# ICAN-7006-USB.net
KiCad netlist of a schematic drawn in Altium Designer
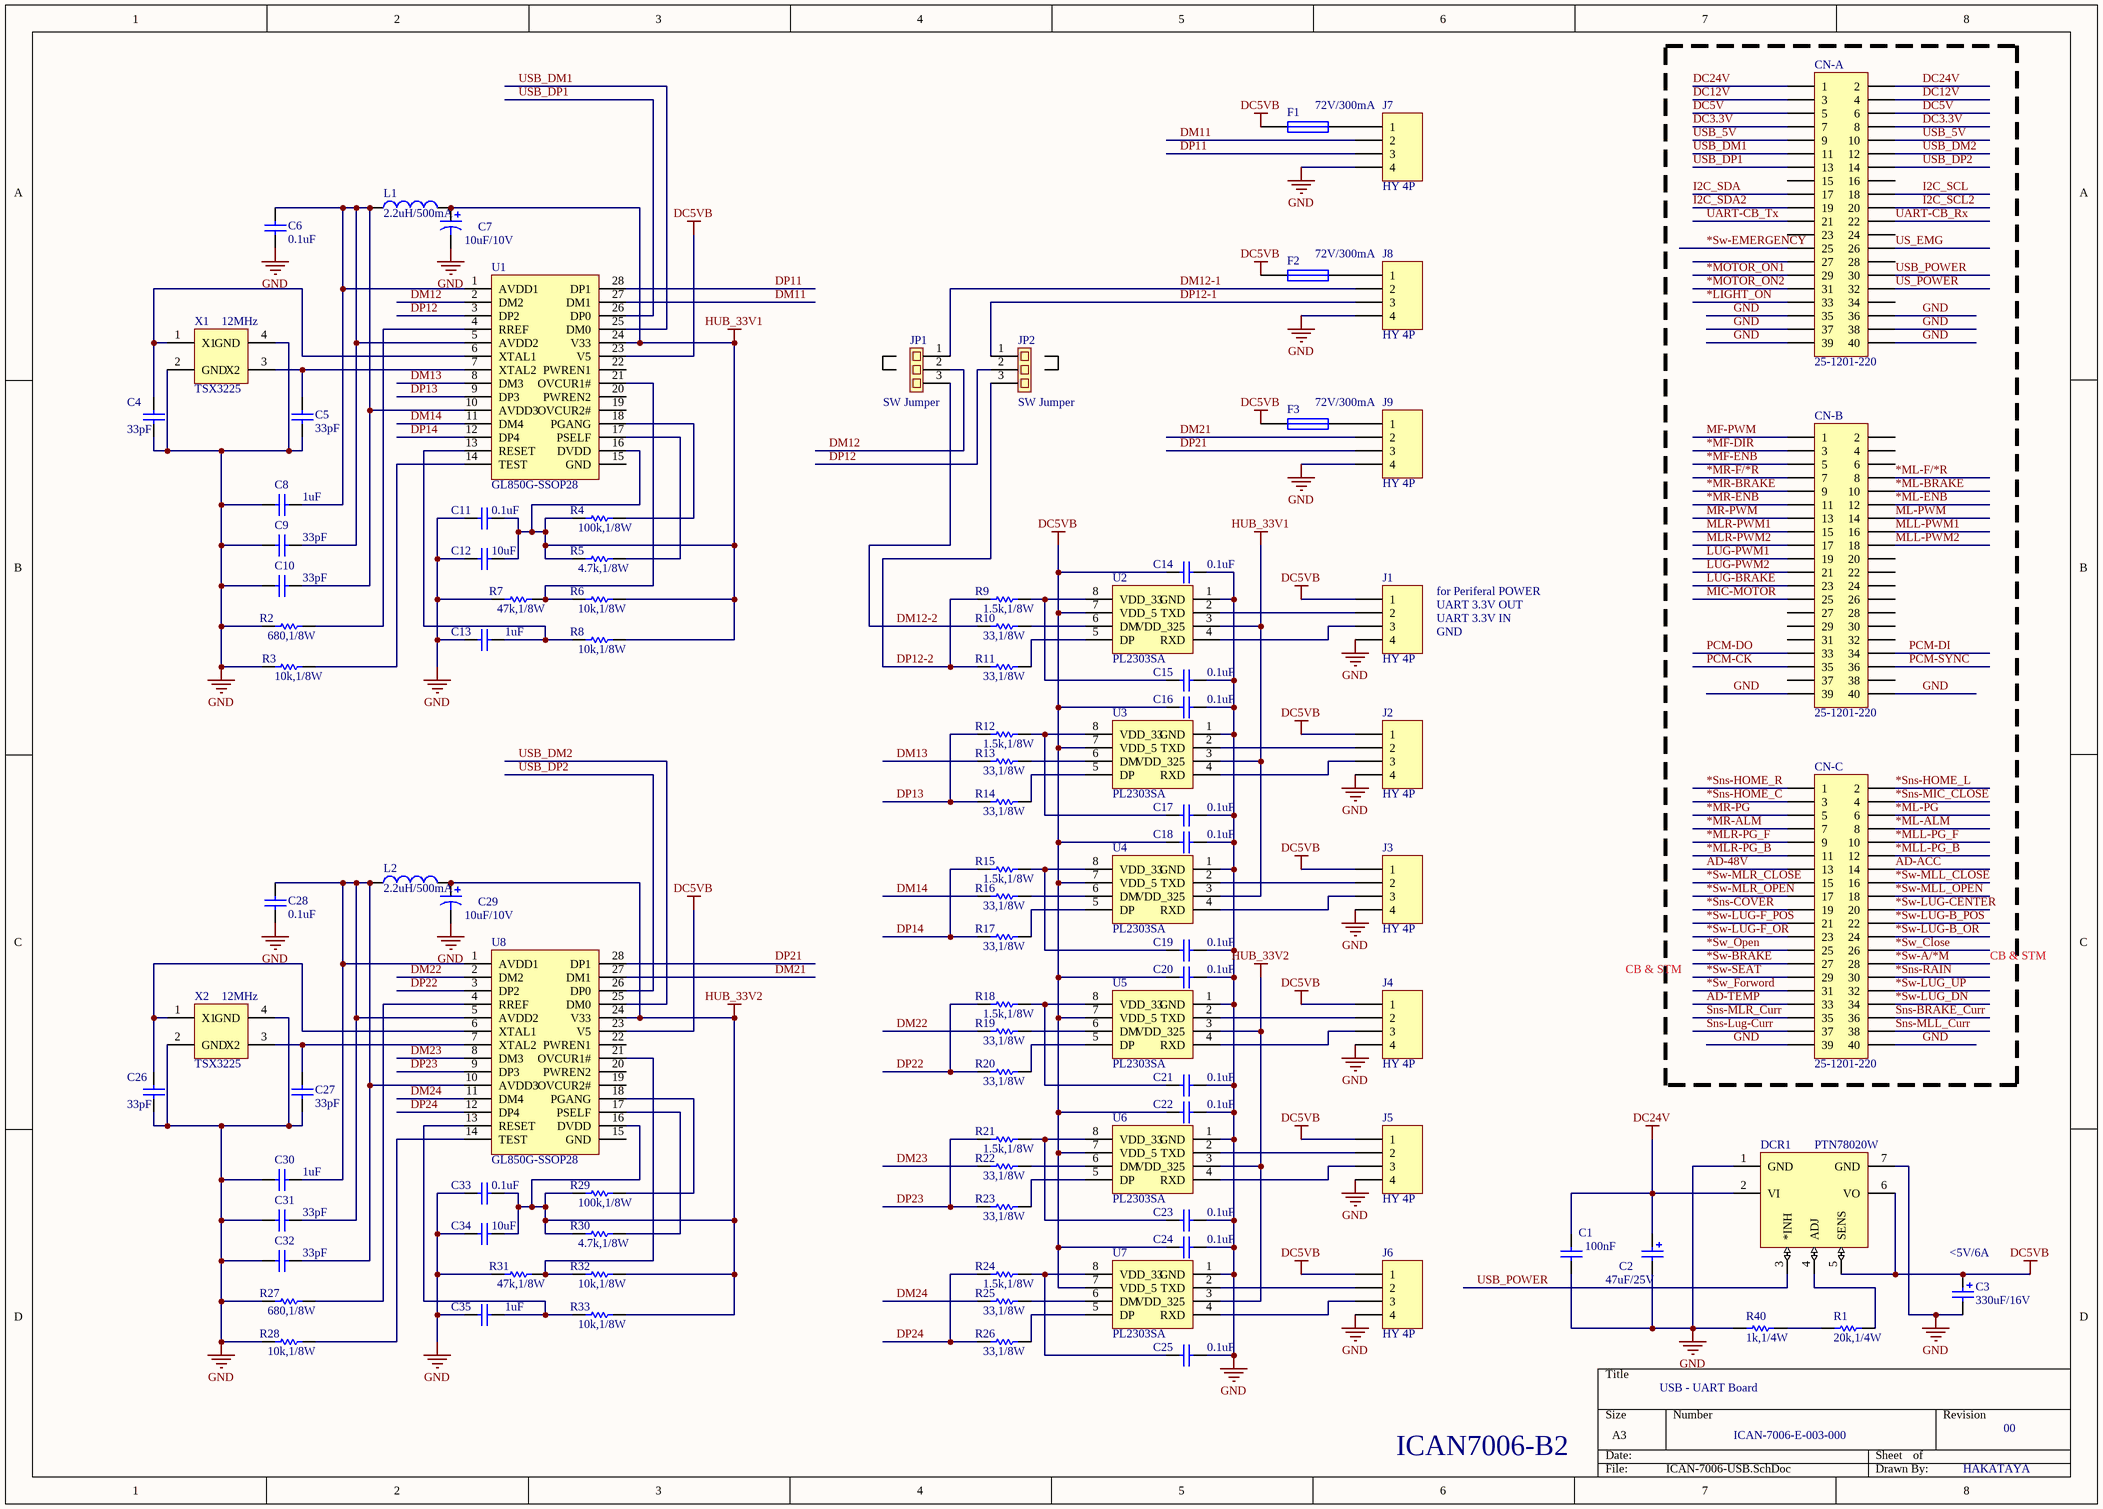
[diagram p0: ICAN-7006-USB.SchDoc]

(export (version "E")
  (design (tool "Eeschema 10.0.6"))
  (components
    (comp (ref "C1")
      (value "100nF")
      (footprint "HAKATAYA:[0805]2012")
      (description "Capacitor")
      (fields (field (name "PUBLISHER") "Altium Limited"))
      (libsource (lib "Miscellaneous Devices") (part "Cap"))
    )
    (comp (ref "C2")
      (value "47uF/25V")
      (footprint "HAKATAYA:Capa MH5 PITCH2.5mm")
      (description "Polarized Capacitor (Axial)")
      (fields (field (name "PUBLISHER") "Altium Limited"))
      (libsource (lib "Miscellaneous Devices") (part "Cap Pol2"))
    )
    (comp (ref "C3")
      (value "330uF/16V")
      (footprint "HAKATAYA:CAPA WXA PITCH 3.5mm")
      (description "Polarized Capacitor (Axial)")
      (fields (field (name "PUBLISHER") "Altium Limited"))
      (libsource (lib "Miscellaneous Devices") (part "Cap Pol2"))
    )
    (comp (ref "C4")
      (value "33pF")
      (footprint "HAKATAYA:[0805]2012")
      (description "Capacitor")
      (fields (field (name "PUBLISHER") "Altium Limited"))
      (libsource (lib "Miscellaneous Devices") (part "Cap Semi"))
    )
    (comp (ref "C5")
      (value "33pF")
      (footprint "HAKATAYA:[0805]2012")
      (description "Capacitor")
      (fields (field (name "PUBLISHER") "Altium Limited"))
      (libsource (lib "Miscellaneous Devices") (part "Cap Semi"))
    )
    (comp (ref "C6")
      (value "0.1uF")
      (footprint "HAKATAYA:[0805]2012")
      (description "Capacitor")
      (fields (field (name "PUBLISHER") "Altium Limited"))
      (libsource (lib "Miscellaneous Devices") (part "Cap Semi"))
    )
    (comp (ref "C7")
      (value "10uF/10V")
      (footprint "[0805]2012")
      (description "Polarized Capacitor (Surface Mount)")
      (fields (field (name "PUBLISHER") "Altium Limited"))
      (libsource (lib "Miscellaneous Devices") (part "Cap Pol3"))
    )
    (comp (ref "C8")
      (value "1uF")
      (footprint "[0805]2012")
      (description "Capacitor")
      (fields (field (name "PUBLISHER") "Altium Limited"))
      (libsource (lib "Miscellaneous Devices") (part "Cap Semi"))
    )
    (comp (ref "C9")
      (value "33pF")
      (footprint "HAKATAYA:[0805]2012")
      (description "Capacitor")
      (fields (field (name "PUBLISHER") "Altium Limited"))
      (libsource (lib "Miscellaneous Devices") (part "Cap Semi"))
    )
    (comp (ref "C10")
      (value "33pF")
      (footprint "HAKATAYA:[0805]2012")
      (description "Capacitor")
      (fields (field (name "PUBLISHER") "Altium Limited"))
      (libsource (lib "Miscellaneous Devices") (part "Cap Semi"))
    )
    (comp (ref "C11")
      (value "0.1uF")
      (footprint "HAKATAYA:[0805]2012")
      (description "Capacitor")
      (fields (field (name "PUBLISHER") "Altium Limited"))
      (libsource (lib "Miscellaneous Devices") (part "Cap Semi"))
    )
    (comp (ref "C12")
      (value "10uF")
      (footprint "[0805]2012")
      (description "Capacitor")
      (fields (field (name "PUBLISHER") "Altium Limited"))
      (libsource (lib "Miscellaneous Devices") (part "Cap Semi"))
    )
    (comp (ref "C13")
      (value "1uF")
      (footprint "[0805]2012")
      (description "Capacitor")
      (fields (field (name "PUBLISHER") "Altium Limited"))
      (libsource (lib "Miscellaneous Devices") (part "Cap Semi"))
    )
    (comp (ref "C14")
      (value "0.1uF")
      (footprint "HAKATAYA:[0805]2012")
      (description "Capacitor")
      (fields (field (name "PUBLISHER") "Altium Limited"))
      (libsource (lib "Miscellaneous Devices") (part "Cap Semi"))
    )
    (comp (ref "C15")
      (value "0.1uF")
      (footprint "HAKATAYA:[0805]2012")
      (description "Capacitor")
      (fields (field (name "PUBLISHER") "Altium Limited"))
      (libsource (lib "Miscellaneous Devices") (part "Cap Semi"))
    )
    (comp (ref "C16")
      (value "0.1uF")
      (footprint "[0805]2012")
      (description "Capacitor")
      (fields (field (name "PUBLISHER") "Altium Limited"))
      (libsource (lib "Miscellaneous Devices") (part "Cap Semi"))
    )
    (comp (ref "C17")
      (value "0.1uF")
      (footprint "[0805]2012")
      (description "Capacitor")
      (fields (field (name "PUBLISHER") "Altium Limited"))
      (libsource (lib "Miscellaneous Devices") (part "Cap Semi"))
    )
    (comp (ref "C18")
      (value "0.1uF")
      (footprint "[0805]2012")
      (description "Capacitor")
      (fields (field (name "PUBLISHER") "Altium Limited"))
      (libsource (lib "Miscellaneous Devices") (part "Cap Semi"))
    )
    (comp (ref "C19")
      (value "0.1uF")
      (footprint "[0805]2012")
      (description "Capacitor")
      (fields (field (name "PUBLISHER") "Altium Limited"))
      (libsource (lib "Miscellaneous Devices") (part "Cap Semi"))
    )
    (comp (ref "C20")
      (value "0.1uF")
      (footprint "[0805]2012")
      (description "Capacitor")
      (fields (field (name "PUBLISHER") "Altium Limited"))
      (libsource (lib "Miscellaneous Devices") (part "Cap Semi"))
    )
    (comp (ref "C21")
      (value "0.1uF")
      (footprint "[0805]2012")
      (description "Capacitor")
      (fields (field (name "PUBLISHER") "Altium Limited"))
      (libsource (lib "Miscellaneous Devices") (part "Cap Semi"))
    )
    (comp (ref "C22")
      (value "0.1uF")
      (footprint "[0805]2012")
      (description "Capacitor")
      (fields (field (name "PUBLISHER") "Altium Limited"))
      (libsource (lib "Miscellaneous Devices") (part "Cap Semi"))
    )
    (comp (ref "C23")
      (value "0.1uF")
      (footprint "[0805]2012")
      (description "Capacitor")
      (fields (field (name "PUBLISHER") "Altium Limited"))
      (libsource (lib "Miscellaneous Devices") (part "Cap Semi"))
    )
    (comp (ref "C24")
      (value "0.1uF")
      (footprint "[0805]2012")
      (description "Capacitor")
      (fields (field (name "PUBLISHER") "Altium Limited"))
      (libsource (lib "Miscellaneous Devices") (part "Cap Semi"))
    )
    (comp (ref "C25")
      (value "0.1uF")
      (footprint "[0805]2012")
      (description "Capacitor")
      (fields (field (name "PUBLISHER") "Altium Limited"))
      (libsource (lib "Miscellaneous Devices") (part "Cap Semi"))
    )
    (comp (ref "C26")
      (value "33pF")
      (footprint "HAKATAYA:[0805]2012")
      (description "Capacitor")
      (fields (field (name "PUBLISHER") "Altium Limited"))
      (libsource (lib "Miscellaneous Devices") (part "Cap Semi"))
    )
    (comp (ref "C27")
      (value "33pF")
      (footprint "HAKATAYA:[0805]2012")
      (description "Capacitor")
      (fields (field (name "PUBLISHER") "Altium Limited"))
      (libsource (lib "Miscellaneous Devices") (part "Cap Semi"))
    )
    (comp (ref "C28")
      (value "0.1uF")
      (footprint "[0805]2012")
      (description "Capacitor")
      (fields (field (name "PUBLISHER") "Altium Limited"))
      (libsource (lib "Miscellaneous Devices") (part "Cap Semi"))
    )
    (comp (ref "C29")
      (value "10uF/10V")
      (footprint "[0805]2012")
      (description "Polarized Capacitor (Surface Mount)")
      (fields (field (name "PUBLISHER") "Altium Limited"))
      (libsource (lib "Miscellaneous Devices") (part "Cap Pol3"))
    )
    (comp (ref "C30")
      (value "1uF")
      (footprint "[0805]2012")
      (description "Capacitor")
      (fields (field (name "PUBLISHER") "Altium Limited"))
      (libsource (lib "Miscellaneous Devices") (part "Cap Semi"))
    )
    (comp (ref "C31")
      (value "33pF")
      (footprint "HAKATAYA:[0805]2012")
      (description "Capacitor")
      (fields (field (name "PUBLISHER") "Altium Limited"))
      (libsource (lib "Miscellaneous Devices") (part "Cap Semi"))
    )
    (comp (ref "C32")
      (value "33pF")
      (footprint "HAKATAYA:[0805]2012")
      (description "Capacitor")
      (fields (field (name "PUBLISHER") "Altium Limited"))
      (libsource (lib "Miscellaneous Devices") (part "Cap Semi"))
    )
    (comp (ref "C33")
      (value "0.1uF")
      (footprint "[0805]2012")
      (description "Capacitor")
      (fields (field (name "PUBLISHER") "Altium Limited"))
      (libsource (lib "Miscellaneous Devices") (part "Cap Semi"))
    )
    (comp (ref "C34")
      (value "10uF")
      (footprint "[0805]2012")
      (description "Capacitor")
      (fields (field (name "PUBLISHER") "Altium Limited"))
      (libsource (lib "Miscellaneous Devices") (part "Cap Semi"))
    )
    (comp (ref "C35")
      (value "1uF")
      (footprint "[0805]2012")
      (description "Capacitor")
      (fields (field (name "PUBLISHER") "Altium Limited"))
      (libsource (lib "Miscellaneous Devices") (part "Cap Semi"))
    )
    (comp (ref "CN-A")
      (value "25-1201-220")
      (footprint "HDR2X20")
      (description "Header, 20-Pin, Dual row")
      (fields (field (name "PUBLISHER") "Altium Limited"))
      (libsource (lib "Miscellaneous Connectors") (part "Header 20X2"))
    )
    (comp (ref "CN-B")
      (value "25-1201-220")
      (footprint "HDR2X20")
      (description "Header, 20-Pin, Dual row")
      (fields (field (name "PUBLISHER") "Altium Limited"))
      (libsource (lib "Miscellaneous Connectors") (part "Header 20X2"))
    )
    (comp (ref "CN-C")
      (value "25-1201-220")
      (footprint "HDR2X20")
      (description "Header, 20-Pin, Dual row")
      (fields (field (name "PUBLISHER") "Altium Limited"))
      (libsource (lib "Miscellaneous Connectors") (part "Header 20X2"))
    )
    (comp (ref "DCR1")
      (value "PTN78020W")
      (footprint "PTN78020")
      (description "REGURATOR")
      (libsource (lib "*") (part "PTN78020"))
    )
    (comp (ref "F1")
      (value "72V/300mA")
      (footprint "Miscellaneous Devices:CAPR5-4X5")
      (description "Fuse")
      (fields (field (name "PUBLISHER") "Altium Limited"))
      (libsource (lib "Miscellaneous Devices") (part "Fuse 1"))
    )
    (comp (ref "F2")
      (value "72V/300mA")
      (footprint "Miscellaneous Devices:CAPR5-4X5")
      (description "Fuse")
      (fields (field (name "PUBLISHER") "Altium Limited"))
      (libsource (lib "Miscellaneous Devices") (part "Fuse 1"))
    )
    (comp (ref "F3")
      (value "72V/300mA")
      (footprint "Miscellaneous Devices:CAPR5-4X5")
      (description "Fuse")
      (fields (field (name "PUBLISHER") "Altium Limited"))
      (libsource (lib "Miscellaneous Devices") (part "Fuse 1"))
    )
    (comp (ref "J1")
      (value "HY 4P")
      (footprint "HAKATAYA:HY-4AW")
      (description "Header, 4-Pin")
      (fields (field (name "PUBLISHER") "Altium Limited"))
      (libsource (lib "Miscellaneous Connectors") (part "Header 4"))
    )
    (comp (ref "J2")
      (value "HY 4P")
      (footprint "HAKATAYA:HY-4AW")
      (description "Header, 4-Pin")
      (fields (field (name "PUBLISHER") "Altium Limited"))
      (libsource (lib "Miscellaneous Connectors") (part "Header 4"))
    )
    (comp (ref "J3")
      (value "HY 4P")
      (footprint "HAKATAYA:HY-4AW")
      (description "Header, 4-Pin")
      (fields (field (name "PUBLISHER") "Altium Limited"))
      (libsource (lib "Miscellaneous Connectors") (part "Header 4"))
    )
    (comp (ref "J4")
      (value "HY 4P")
      (footprint "HAKATAYA:HY-4AW")
      (description "Header, 4-Pin")
      (fields (field (name "PUBLISHER") "Altium Limited"))
      (libsource (lib "Miscellaneous Connectors") (part "Header 4"))
    )
    (comp (ref "J5")
      (value "HY 4P")
      (footprint "HAKATAYA:HY-4AW")
      (description "Header, 4-Pin")
      (fields (field (name "PUBLISHER") "Altium Limited"))
      (libsource (lib "Miscellaneous Connectors") (part "Header 4"))
    )
    (comp (ref "J6")
      (value "HY 4P")
      (footprint "HAKATAYA:HY-4AW")
      (description "Header, 4-Pin")
      (fields (field (name "PUBLISHER") "Altium Limited"))
      (libsource (lib "Miscellaneous Connectors") (part "Header 4"))
    )
    (comp (ref "J7")
      (value "HY 4P")
      (footprint "HAKATAYA:HY-4AW")
      (description "Header, 4-Pin")
      (fields (field (name "PUBLISHER") "Altium Limited"))
      (libsource (lib "Miscellaneous Connectors") (part "Header 4"))
    )
    (comp (ref "J8")
      (value "HY 4P")
      (footprint "HAKATAYA:HY-4AW")
      (description "Header, 4-Pin")
      (fields (field (name "PUBLISHER") "Altium Limited"))
      (libsource (lib "Miscellaneous Connectors") (part "Header 4"))
    )
    (comp (ref "J9")
      (value "HY 4P")
      (footprint "HAKATAYA:HY-4AW")
      (description "Header, 4-Pin")
      (fields (field (name "PUBLISHER") "Altium Limited"))
      (libsource (lib "Miscellaneous Connectors") (part "Header 4"))
    )
    (comp (ref "JP1")
      (value "SW Jumper")
      (footprint "VR")
      (description "Jumper")
      (libsource (lib "") (part "SW Jumper_1"))
    )
    (comp (ref "JP2")
      (value "SW Jumper")
      (footprint "VR")
      (description "Jumper")
      (libsource (lib "HAKATAYA") (part "SW Jumper"))
    )
    (comp (ref "L1")
      (value "2.2uH/500mA")
      (footprint "HAKATAYA:[0805]2012")
      (description "Inductor")
      (fields (field (name "PUBLISHER") "Altium Limited"))
      (libsource (lib "Miscellaneous Devices") (part "Inductor"))
    )
    (comp (ref "L2")
      (value "2.2uH/500mA")
      (footprint "HAKATAYA:[0805]2012")
      (description "Inductor")
      (fields (field (name "PUBLISHER") "Altium Limited"))
      (libsource (lib "Miscellaneous Devices") (part "Inductor"))
    )
    (comp (ref "R1")
      (value "20k,1/4W")
      (footprint "[1206]3216")
      (description "Resistor")
      (fields (field (name "PUBLISHER") "Altium Limited"))
      (libsource (lib "Miscellaneous Devices") (part "Res1"))
    )
    (comp (ref "R2")
      (value "680,1/8W")
      (footprint "HAKATAYA:[0805]2012")
      (description "Resistor")
      (fields (field (name "PUBLISHER") "Altium Limited"))
      (libsource (lib "Miscellaneous Devices") (part "Res1"))
    )
    (comp (ref "R3")
      (value "10k,1/8W")
      (footprint "HAKATAYA:[0805]2012")
      (description "Resistor")
      (fields (field (name "PUBLISHER") "Altium Limited"))
      (libsource (lib "Miscellaneous Devices") (part "Res1"))
    )
    (comp (ref "R4")
      (value "100k,1/8W")
      (footprint "HAKATAYA:[0805]2012")
      (description "Resistor")
      (fields (field (name "PUBLISHER") "Altium Limited"))
      (libsource (lib "Miscellaneous Devices") (part "Res1"))
    )
    (comp (ref "R5")
      (value "4.7k,1/8W")
      (footprint "HAKATAYA:[0805]2012")
      (description "Resistor")
      (fields (field (name "PUBLISHER") "Altium Limited"))
      (libsource (lib "Miscellaneous Devices") (part "Res1"))
    )
    (comp (ref "R6")
      (value "10k,1/8W")
      (footprint "HAKATAYA:[0805]2012")
      (description "Resistor")
      (fields (field (name "PUBLISHER") "Altium Limited"))
      (libsource (lib "Miscellaneous Devices") (part "Res1"))
    )
    (comp (ref "R7")
      (value "47k,1/8W")
      (footprint "HAKATAYA:[0805]2012")
      (description "Resistor")
      (fields (field (name "PUBLISHER") "Altium Limited"))
      (libsource (lib "Miscellaneous Devices") (part "Res1"))
    )
    (comp (ref "R8")
      (value "10k,1/8W")
      (footprint "HAKATAYA:[0805]2012")
      (description "Resistor")
      (fields (field (name "PUBLISHER") "Altium Limited"))
      (libsource (lib "Miscellaneous Devices") (part "Res1"))
    )
    (comp (ref "R9")
      (value "1.5k,1/8W")
      (footprint "HAKATAYA:[0805]2012")
      (description "Resistor")
      (fields (field (name "PUBLISHER") "Altium Limited"))
      (libsource (lib "Miscellaneous Devices") (part "Res1"))
    )
    (comp (ref "R10")
      (value "33,1/8W")
      (footprint "HAKATAYA:[0805]2012")
      (description "Resistor")
      (fields (field (name "PUBLISHER") "Altium Limited"))
      (libsource (lib "Miscellaneous Devices") (part "Res1"))
    )
    (comp (ref "R11")
      (value "33,1/8W")
      (footprint "HAKATAYA:[0805]2012")
      (description "Resistor")
      (fields (field (name "PUBLISHER") "Altium Limited"))
      (libsource (lib "Miscellaneous Devices") (part "Res1"))
    )
    (comp (ref "R12")
      (value "1.5k,1/8W")
      (footprint "HAKATAYA:[0805]2012")
      (description "Resistor")
      (fields (field (name "PUBLISHER") "Altium Limited"))
      (libsource (lib "Miscellaneous Devices") (part "Res1"))
    )
    (comp (ref "R13")
      (value "33,1/8W")
      (footprint "HAKATAYA:[0805]2012")
      (description "Resistor")
      (fields (field (name "PUBLISHER") "Altium Limited"))
      (libsource (lib "Miscellaneous Devices") (part "Res1"))
    )
    (comp (ref "R14")
      (value "33,1/8W")
      (footprint "HAKATAYA:[0805]2012")
      (description "Resistor")
      (fields (field (name "PUBLISHER") "Altium Limited"))
      (libsource (lib "Miscellaneous Devices") (part "Res1"))
    )
    (comp (ref "R15")
      (value "1.5k,1/8W")
      (footprint "HAKATAYA:[0805]2012")
      (description "Resistor")
      (fields (field (name "PUBLISHER") "Altium Limited"))
      (libsource (lib "Miscellaneous Devices") (part "Res1"))
    )
    (comp (ref "R16")
      (value "33,1/8W")
      (footprint "HAKATAYA:[0805]2012")
      (description "Resistor")
      (fields (field (name "PUBLISHER") "Altium Limited"))
      (libsource (lib "Miscellaneous Devices") (part "Res1"))
    )
    (comp (ref "R17")
      (value "33,1/8W")
      (footprint "HAKATAYA:[0805]2012")
      (description "Resistor")
      (fields (field (name "PUBLISHER") "Altium Limited"))
      (libsource (lib "Miscellaneous Devices") (part "Res1"))
    )
    (comp (ref "R18")
      (value "1.5k,1/8W")
      (footprint "HAKATAYA:[0805]2012")
      (description "Resistor")
      (fields (field (name "PUBLISHER") "Altium Limited"))
      (libsource (lib "Miscellaneous Devices") (part "Res1"))
    )
    (comp (ref "R19")
      (value "33,1/8W")
      (footprint "HAKATAYA:[0805]2012")
      (description "Resistor")
      (fields (field (name "PUBLISHER") "Altium Limited"))
      (libsource (lib "Miscellaneous Devices") (part "Res1"))
    )
    (comp (ref "R20")
      (value "33,1/8W")
      (footprint "HAKATAYA:[0805]2012")
      (description "Resistor")
      (fields (field (name "PUBLISHER") "Altium Limited"))
      (libsource (lib "Miscellaneous Devices") (part "Res1"))
    )
    (comp (ref "R21")
      (value "1.5k,1/8W")
      (footprint "HAKATAYA:[0805]2012")
      (description "Resistor")
      (fields (field (name "PUBLISHER") "Altium Limited"))
      (libsource (lib "Miscellaneous Devices") (part "Res1"))
    )
    (comp (ref "R22")
      (value "33,1/8W")
      (footprint "HAKATAYA:[0805]2012")
      (description "Resistor")
      (fields (field (name "PUBLISHER") "Altium Limited"))
      (libsource (lib "Miscellaneous Devices") (part "Res1"))
    )
    (comp (ref "R23")
      (value "33,1/8W")
      (footprint "HAKATAYA:[0805]2012")
      (description "Resistor")
      (fields (field (name "PUBLISHER") "Altium Limited"))
      (libsource (lib "Miscellaneous Devices") (part "Res1"))
    )
    (comp (ref "R24")
      (value "1.5k,1/8W")
      (footprint "HAKATAYA:[0805]2012")
      (description "Resistor")
      (fields (field (name "PUBLISHER") "Altium Limited"))
      (libsource (lib "Miscellaneous Devices") (part "Res1"))
    )
    (comp (ref "R25")
      (value "33,1/8W")
      (footprint "HAKATAYA:[0805]2012")
      (description "Resistor")
      (fields (field (name "PUBLISHER") "Altium Limited"))
      (libsource (lib "Miscellaneous Devices") (part "Res1"))
    )
    (comp (ref "R26")
      (value "33,1/8W")
      (footprint "HAKATAYA:[0805]2012")
      (description "Resistor")
      (fields (field (name "PUBLISHER") "Altium Limited"))
      (libsource (lib "Miscellaneous Devices") (part "Res1"))
    )
    (comp (ref "R27")
      (value "680,1/8W")
      (footprint "HAKATAYA:[0805]2012")
      (description "Resistor")
      (fields (field (name "PUBLISHER") "Altium Limited"))
      (libsource (lib "Miscellaneous Devices") (part "Res1"))
    )
    (comp (ref "R28")
      (value "10k,1/8W")
      (footprint "HAKATAYA:[0805]2012")
      (description "Resistor")
      (fields (field (name "PUBLISHER") "Altium Limited"))
      (libsource (lib "Miscellaneous Devices") (part "Res1"))
    )
    (comp (ref "R29")
      (value "100k,1/8W")
      (footprint "HAKATAYA:[0805]2012")
      (description "Resistor")
      (fields (field (name "PUBLISHER") "Altium Limited"))
      (libsource (lib "Miscellaneous Devices") (part "Res1"))
    )
    (comp (ref "R30")
      (value "4.7k,1/8W")
      (footprint "HAKATAYA:[0805]2012")
      (description "Resistor")
      (fields (field (name "PUBLISHER") "Altium Limited"))
      (libsource (lib "Miscellaneous Devices") (part "Res1"))
    )
    (comp (ref "R31")
      (value "47k,1/8W")
      (footprint "HAKATAYA:[0805]2012")
      (description "Resistor")
      (fields (field (name "PUBLISHER") "Altium Limited"))
      (libsource (lib "Miscellaneous Devices") (part "Res1"))
    )
    (comp (ref "R32")
      (value "10k,1/8W")
      (footprint "HAKATAYA:[0805]2012")
      (description "Resistor")
      (fields (field (name "PUBLISHER") "Altium Limited"))
      (libsource (lib "Miscellaneous Devices") (part "Res1"))
    )
    (comp (ref "R33")
      (value "10k,1/8W")
      (footprint "HAKATAYA:[0805]2012")
      (description "Resistor")
      (fields (field (name "PUBLISHER") "Altium Limited"))
      (libsource (lib "Miscellaneous Devices") (part "Res1"))
    )
    (comp (ref "R40")
      (value "1k,1/4W")
      (footprint "[1206]3216")
      (description "Resistor")
      (fields (field (name "PUBLISHER") "Altium Limited"))
      (libsource (lib "Miscellaneous Devices") (part "Res1"))
    )
    (comp (ref "U1")
      (value "GL850G-SSOP28")
      (footprint "Microchip Footprints:SSOP-28")
      (description "HUB Controller")
      (libsource (lib "HAKATAYA") (part "IC28"))
    )
    (comp (ref "U2")
      (value "PL2303SA")
      (footprint "Microchip Footprints:SOIC150-8_L")
      (description "Serial Bridge")
      (libsource (lib "HAKATAYA") (part "IC8-WIDE"))
    )
    (comp (ref "U3")
      (value "PL2303SA")
      (footprint "Microchip Footprints:SOIC150-8_L")
      (description "Serial Bridge")
      (libsource (lib "HAKATAYA") (part "IC8-WIDE"))
    )
    (comp (ref "U4")
      (value "PL2303SA")
      (footprint "Microchip Footprints:SOIC150-8_L")
      (description "Serial Bridge")
      (libsource (lib "HAKATAYA") (part "IC8-WIDE"))
    )
    (comp (ref "U5")
      (value "PL2303SA")
      (footprint "Microchip Footprints:SOIC150-8_L")
      (description "Serial Bridge")
      (libsource (lib "HAKATAYA") (part "IC8-WIDE"))
    )
    (comp (ref "U6")
      (value "PL2303SA")
      (footprint "Microchip Footprints:SOIC150-8_L")
      (description "Serial Bridge")
      (libsource (lib "HAKATAYA") (part "IC8-WIDE"))
    )
    (comp (ref "U7")
      (value "PL2303SA")
      (footprint "Microchip Footprints:SOIC150-8_L")
      (description "Serial Bridge")
      (libsource (lib "HAKATAYA") (part "IC8-WIDE"))
    )
    (comp (ref "U8")
      (value "GL850G-SSOP28")
      (footprint "Microchip Footprints:SSOP-28")
      (libsource (lib "HAKATAYA") (part "IC28"))
    )
    (comp (ref "X1")
      (value "TSX3225")
      (footprint "HAKATAYA:XTAL 3225")
      (description "Crystal Oscillator")
      (libsource (lib "HAKATAYA") (part "IC4 WIDE"))
    )
    (comp (ref "X2")
      (value "TSX3225")
      (footprint "HAKATAYA:XTAL 3225")
      (description "Crystal Oscillator")
      (libsource (lib "HAKATAYA") (part "IC4 WIDE"))
    )
  )
  (nets
    (net (code "1") (name "/*LIGHT_ON") (class "Default")
      (node (ref "CN-A") (pin "33") (pinfunction "33_33") (pintype "passive"))
    )
    (net (code "2") (name "/*MF-DIR") (class "Default")
      (node (ref "CN-B") (pin "3") (pinfunction "3_3") (pintype "passive"))
    )
    (net (code "3") (name "/*MF-ENB") (class "Default")
      (node (ref "CN-B") (pin "5") (pinfunction "5_5") (pintype "passive"))
    )
    (net (code "4") (name "/*ML-ALM") (class "Default")
      (node (ref "CN-C") (pin "8") (pinfunction "8_8") (pintype "passive"))
    )
    (net (code "5") (name "/*ML-BRAKE") (class "Default")
      (node (ref "CN-B") (pin "10") (pinfunction "10_10") (pintype "passive"))
    )
    (net (code "6") (name "/*ML-ENB") (class "Default")
      (node (ref "CN-B") (pin "12") (pinfunction "12_12") (pintype "passive"))
    )
    (net (code "7") (name "/*ML-F{slash}*R") (class "Default")
      (node (ref "CN-B") (pin "8") (pinfunction "8_8") (pintype "passive"))
    )
    (net (code "8") (name "/*ML-PG") (class "Default")
      (node (ref "CN-C") (pin "6") (pinfunction "6_6") (pintype "passive"))
    )
    (net (code "9") (name "/*MLL-PG_B") (class "Default")
      (node (ref "CN-C") (pin "12") (pinfunction "12_12") (pintype "passive"))
    )
    (net (code "10") (name "/*MLL-PG_F") (class "Default")
      (node (ref "CN-C") (pin "10") (pinfunction "10_10") (pintype "passive"))
    )
    (net (code "11") (name "/*MLR-PG_B") (class "Default")
      (node (ref "CN-C") (pin "11") (pinfunction "11_11") (pintype "passive"))
    )
    (net (code "12") (name "/*MLR-PG_F") (class "Default")
      (node (ref "CN-C") (pin "9") (pinfunction "9_9") (pintype "passive"))
    )
    (net (code "13") (name "/*MOTOR_ON1") (class "Default")
      (node (ref "CN-A") (pin "29") (pinfunction "29_29") (pintype "passive"))
    )
    (net (code "14") (name "/*MOTOR_ON2") (class "Default")
      (node (ref "CN-A") (pin "31") (pinfunction "31_31") (pintype "passive"))
    )
    (net (code "15") (name "/*MR-ALM") (class "Default")
      (node (ref "CN-C") (pin "7") (pinfunction "7_7") (pintype "passive"))
    )
    (net (code "16") (name "/*MR-BRAKE") (class "Default")
      (node (ref "CN-B") (pin "9") (pinfunction "9_9") (pintype "passive"))
    )
    (net (code "17") (name "/*MR-ENB") (class "Default")
      (node (ref "CN-B") (pin "11") (pinfunction "11_11") (pintype "passive"))
    )
    (net (code "18") (name "/*MR-F{slash}*R") (class "Default")
      (node (ref "CN-B") (pin "7") (pinfunction "7_7") (pintype "passive"))
    )
    (net (code "19") (name "/*MR-PG") (class "Default")
      (node (ref "CN-C") (pin "5") (pinfunction "5_5") (pintype "passive"))
    )
    (net (code "20") (name "/*Sns-COVER") (class "Default")
      (node (ref "CN-C") (pin "19") (pinfunction "19_19") (pintype "passive"))
    )
    (net (code "21") (name "/*Sns-HOME_C") (class "Default")
      (node (ref "CN-C") (pin "3") (pinfunction "3_3") (pintype "passive"))
    )
    (net (code "22") (name "/*Sns-HOME_L") (class "Default")
      (node (ref "CN-C") (pin "2") (pinfunction "2_2") (pintype "passive"))
    )
    (net (code "23") (name "/*Sns-HOME_R") (class "Default")
      (node (ref "CN-C") (pin "1") (pinfunction "1_1") (pintype "passive"))
    )
    (net (code "24") (name "/*Sns-MIC_CLOSE") (class "Default")
      (node (ref "CN-C") (pin "4") (pinfunction "4_4") (pintype "passive"))
    )
    (net (code "25") (name "/*Sns-RAIN") (class "Default")
      (node (ref "CN-C") (pin "30") (pinfunction "30_30") (pintype "passive"))
    )
    (net (code "26") (name "/*Sw-A{slash}*M") (class "Default")
      (node (ref "CN-C") (pin "28") (pinfunction "28_28") (pintype "passive"))
    )
    (net (code "27") (name "/*Sw-BRAKE") (class "Default")
      (node (ref "CN-C") (pin "27") (pinfunction "27_27") (pintype "passive"))
    )
    (net (code "28") (name "/*Sw-EMERGENCY") (class "Default")
      (node (ref "CN-A") (pin "25") (pinfunction "25_25") (pintype "passive"))
    )
    (net (code "29") (name "/*Sw-LUG-B_OR") (class "Default")
      (node (ref "CN-C") (pin "24") (pinfunction "24_24") (pintype "passive"))
    )
    (net (code "30") (name "/*Sw-LUG-B_POS") (class "Default")
      (node (ref "CN-C") (pin "22") (pinfunction "22_22") (pintype "passive"))
    )
    (net (code "31") (name "/*Sw-LUG-CENTER") (class "Default")
      (node (ref "CN-C") (pin "20") (pinfunction "20_20") (pintype "passive"))
    )
    (net (code "32") (name "/*Sw-LUG-F_OR") (class "Default")
      (node (ref "CN-C") (pin "23") (pinfunction "23_23") (pintype "passive"))
    )
    (net (code "33") (name "/*Sw-LUG-F_POS") (class "Default")
      (node (ref "CN-C") (pin "21") (pinfunction "21_21") (pintype "passive"))
    )
    (net (code "34") (name "/*Sw-LUG_DN") (class "Default")
      (node (ref "CN-C") (pin "34") (pinfunction "34_34") (pintype "passive"))
    )
    (net (code "35") (name "/*Sw-LUG_UP") (class "Default")
      (node (ref "CN-C") (pin "32") (pinfunction "32_32") (pintype "passive"))
    )
    (net (code "36") (name "/*Sw-MLL_CLOSE") (class "Default")
      (node (ref "CN-C") (pin "16") (pinfunction "16_16") (pintype "passive"))
    )
    (net (code "37") (name "/*Sw-MLL_OPEN") (class "Default")
      (node (ref "CN-C") (pin "18") (pinfunction "18_18") (pintype "passive"))
    )
    (net (code "38") (name "/*Sw-MLR_CLOSE") (class "Default")
      (node (ref "CN-C") (pin "15") (pinfunction "15_15") (pintype "passive"))
    )
    (net (code "39") (name "/*Sw-MLR_OPEN") (class "Default")
      (node (ref "CN-C") (pin "17") (pinfunction "17_17") (pintype "passive"))
    )
    (net (code "40") (name "/*Sw-SEAT") (class "Default")
      (node (ref "CN-C") (pin "29") (pinfunction "29_29") (pintype "passive"))
    )
    (net (code "41") (name "/*Sw_Close") (class "Default")
      (node (ref "CN-C") (pin "26") (pinfunction "26_26") (pintype "passive"))
    )
    (net (code "42") (name "/*Sw_Forword") (class "Default")
      (node (ref "CN-C") (pin "31") (pinfunction "31_31") (pintype "passive"))
    )
    (net (code "43") (name "/*Sw_Open") (class "Default")
      (node (ref "CN-C") (pin "25") (pinfunction "25_25") (pintype "passive"))
    )
    (net (code "44") (name "/AD-48V") (class "Default")
      (node (ref "CN-C") (pin "13") (pinfunction "13_13") (pintype "passive"))
    )
    (net (code "45") (name "/AD-ACC") (class "Default")
      (node (ref "CN-C") (pin "14") (pinfunction "14_14") (pintype "passive"))
    )
    (net (code "46") (name "/AD-TEMP") (class "Default")
      (node (ref "CN-C") (pin "33") (pinfunction "33_33") (pintype "passive"))
    )
    (net (code "47") (name "/DC3.3V") (class "Default")
      (node (ref "CN-A") (pin "7") (pinfunction "7_7") (pintype "passive"))
      (node (ref "CN-A") (pin "8") (pinfunction "8_8") (pintype "passive"))
    )
    (net (code "48") (name "/DC5V") (class "Default")
      (node (ref "CN-A") (pin "5") (pinfunction "5_5") (pintype "passive"))
      (node (ref "CN-A") (pin "6") (pinfunction "6_6") (pintype "passive"))
    )
    (net (code "49") (name "/DC12V") (class "Default")
      (node (ref "CN-A") (pin "3") (pinfunction "3_3") (pintype "passive"))
      (node (ref "CN-A") (pin "4") (pinfunction "4_4") (pintype "passive"))
    )
    (net (code "50") (name "/DM11") (class "Default")
      (node (ref "J7") (pin "2") (pinfunction "2_2") (pintype "passive"))
      (node (ref "U1") (pin "27") (pinfunction "DM1_27") (pintype "passive"))
    )
    (net (code "51") (name "/DM12") (class "Default")
      (node (ref "JP1") (pin "2") (pinfunction "2_2") (pintype "passive"))
      (node (ref "U1") (pin "2") (pinfunction "DM2_2") (pintype "passive"))
    )
    (net (code "52") (name "/DM12-1") (class "Default")
      (node (ref "J8") (pin "2") (pinfunction "2_2") (pintype "passive"))
      (node (ref "JP1") (pin "1") (pinfunction "1_1") (pintype "passive"))
    )
    (net (code "53") (name "/DM12-2") (class "Default")
      (node (ref "JP1") (pin "3") (pinfunction "4_3") (pintype "passive"))
      (node (ref "R10") (pin "1") (pinfunction "1_1") (pintype "passive"))
    )
    (net (code "54") (name "/DM13") (class "Default")
      (node (ref "R13") (pin "1") (pinfunction "1_1") (pintype "passive"))
      (node (ref "U1") (pin "8") (pinfunction "DM3_8") (pintype "passive"))
    )
    (net (code "55") (name "/DM14") (class "Default")
      (node (ref "R16") (pin "1") (pinfunction "1_1") (pintype "passive"))
      (node (ref "U1") (pin "11") (pinfunction "DM4_11") (pintype "passive"))
    )
    (net (code "56") (name "/DM21") (class "Default")
      (node (ref "J9") (pin "2") (pinfunction "2_2") (pintype "passive"))
      (node (ref "U8") (pin "27") (pinfunction "DM1_27") (pintype "passive"))
    )
    (net (code "57") (name "/DM22") (class "Default")
      (node (ref "R19") (pin "1") (pinfunction "1_1") (pintype "passive"))
      (node (ref "U8") (pin "2") (pinfunction "DM2_2") (pintype "passive"))
    )
    (net (code "58") (name "/DM23") (class "Default")
      (node (ref "R22") (pin "1") (pinfunction "1_1") (pintype "passive"))
      (node (ref "U8") (pin "8") (pinfunction "DM3_8") (pintype "passive"))
    )
    (net (code "59") (name "/DM24") (class "Default")
      (node (ref "R25") (pin "1") (pinfunction "1_1") (pintype "passive"))
      (node (ref "U8") (pin "11") (pinfunction "DM4_11") (pintype "passive"))
    )
    (net (code "60") (name "/DP11") (class "Default")
      (node (ref "J7") (pin "3") (pinfunction "3_3") (pintype "passive"))
      (node (ref "U1") (pin "28") (pinfunction "DP1_28") (pintype "passive"))
    )
    (net (code "61") (name "/DP12") (class "Default")
      (node (ref "JP2") (pin "2") (pinfunction "2_2") (pintype "passive"))
      (node (ref "U1") (pin "3") (pinfunction "DP2_3") (pintype "passive"))
    )
    (net (code "62") (name "/DP12-1") (class "Default")
      (node (ref "J8") (pin "3") (pinfunction "3_3") (pintype "passive"))
      (node (ref "JP2") (pin "1") (pinfunction "1_1") (pintype "passive"))
    )
    (net (code "63") (name "/DP12-2") (class "Default")
      (node (ref "JP2") (pin "3") (pinfunction "4_3") (pintype "passive"))
      (node (ref "R11") (pin "1") (pinfunction "1_1") (pintype "passive"))
      (node (ref "R9") (pin "1") (pinfunction "1_1") (pintype "passive"))
    )
    (net (code "64") (name "/DP13") (class "Default")
      (node (ref "R12") (pin "1") (pinfunction "1_1") (pintype "passive"))
      (node (ref "R14") (pin "1") (pinfunction "1_1") (pintype "passive"))
      (node (ref "U1") (pin "9") (pinfunction "DP3_9") (pintype "passive"))
    )
    (net (code "65") (name "/DP14") (class "Default")
      (node (ref "R15") (pin "1") (pinfunction "1_1") (pintype "passive"))
      (node (ref "R17") (pin "1") (pinfunction "1_1") (pintype "passive"))
      (node (ref "U1") (pin "12") (pinfunction "DP4_12") (pintype "passive"))
    )
    (net (code "66") (name "/DP21") (class "Default")
      (node (ref "J9") (pin "3") (pinfunction "3_3") (pintype "passive"))
      (node (ref "U8") (pin "28") (pinfunction "DP1_28") (pintype "passive"))
    )
    (net (code "67") (name "/DP22") (class "Default")
      (node (ref "R18") (pin "1") (pinfunction "1_1") (pintype "passive"))
      (node (ref "R20") (pin "1") (pinfunction "1_1") (pintype "passive"))
      (node (ref "U8") (pin "3") (pinfunction "DP2_3") (pintype "passive"))
    )
    (net (code "68") (name "/DP23") (class "Default")
      (node (ref "R21") (pin "1") (pinfunction "1_1") (pintype "passive"))
      (node (ref "R23") (pin "1") (pinfunction "1_1") (pintype "passive"))
      (node (ref "U8") (pin "9") (pinfunction "DP3_9") (pintype "passive"))
    )
    (net (code "69") (name "/DP24") (class "Default")
      (node (ref "R24") (pin "1") (pinfunction "1_1") (pintype "passive"))
      (node (ref "R26") (pin "1") (pinfunction "1_1") (pintype "passive"))
      (node (ref "U8") (pin "12") (pinfunction "DP4_12") (pintype "passive"))
    )
    (net (code "70") (name "/I2C_SCL") (class "Default")
      (node (ref "CN-A") (pin "18") (pinfunction "18_18") (pintype "passive"))
    )
    (net (code "71") (name "/I2C_SCL2") (class "Default")
      (node (ref "CN-A") (pin "20") (pinfunction "20_20") (pintype "passive"))
    )
    (net (code "72") (name "/I2C_SDA") (class "Default")
      (node (ref "CN-A") (pin "17") (pinfunction "17_17") (pintype "passive"))
    )
    (net (code "73") (name "/I2C_SDA2") (class "Default")
      (node (ref "CN-A") (pin "19") (pinfunction "19_19") (pintype "passive"))
    )
    (net (code "74") (name "/LUG-BRAKE") (class "Default")
      (node (ref "CN-B") (pin "23") (pinfunction "23_23") (pintype "passive"))
    )
    (net (code "75") (name "/LUG-PWM1") (class "Default")
      (node (ref "CN-B") (pin "19") (pinfunction "19_19") (pintype "passive"))
    )
    (net (code "76") (name "/LUG-PWM2") (class "Default")
      (node (ref "CN-B") (pin "21") (pinfunction "21_21") (pintype "passive"))
    )
    (net (code "77") (name "/MF-PWM") (class "Default")
      (node (ref "CN-B") (pin "1") (pinfunction "1_1") (pintype "passive"))
    )
    (net (code "78") (name "/MIC-MOTOR") (class "Default")
      (node (ref "CN-B") (pin "25") (pinfunction "25_25") (pintype "passive"))
    )
    (net (code "79") (name "/ML-PWM") (class "Default")
      (node (ref "CN-B") (pin "14") (pinfunction "14_14") (pintype "passive"))
    )
    (net (code "80") (name "/MLL-PWM1") (class "Default")
      (node (ref "CN-B") (pin "16") (pinfunction "16_16") (pintype "passive"))
    )
    (net (code "81") (name "/MLL-PWM2") (class "Default")
      (node (ref "CN-B") (pin "18") (pinfunction "18_18") (pintype "passive"))
    )
    (net (code "82") (name "/MLR-PWM1") (class "Default")
      (node (ref "CN-B") (pin "15") (pinfunction "15_15") (pintype "passive"))
    )
    (net (code "83") (name "/MLR-PWM2") (class "Default")
      (node (ref "CN-B") (pin "17") (pinfunction "17_17") (pintype "passive"))
    )
    (net (code "84") (name "/MR-PWM") (class "Default")
      (node (ref "CN-B") (pin "13") (pinfunction "13_13") (pintype "passive"))
    )
    (net (code "85") (name "/PCM-CK") (class "Default")
      (node (ref "CN-B") (pin "35") (pinfunction "35_35") (pintype "passive"))
    )
    (net (code "86") (name "/PCM-DI") (class "Default")
      (node (ref "CN-B") (pin "34") (pinfunction "34_34") (pintype "passive"))
    )
    (net (code "87") (name "/PCM-DO") (class "Default")
      (node (ref "CN-B") (pin "33") (pinfunction "33_33") (pintype "passive"))
    )
    (net (code "88") (name "/PCM-SYNC") (class "Default")
      (node (ref "CN-B") (pin "36") (pinfunction "36_36") (pintype "passive"))
    )
    (net (code "89") (name "/Sns-BRAKE_Curr") (class "Default")
      (node (ref "CN-C") (pin "36") (pinfunction "36_36") (pintype "passive"))
    )
    (net (code "90") (name "/Sns-Lug-Curr") (class "Default")
      (node (ref "CN-C") (pin "37") (pinfunction "37_37") (pintype "passive"))
    )
    (net (code "91") (name "/Sns-MLL_Curr") (class "Default")
      (node (ref "CN-C") (pin "38") (pinfunction "38_38") (pintype "passive"))
    )
    (net (code "92") (name "/Sns-MLR_Curr") (class "Default")
      (node (ref "CN-C") (pin "35") (pinfunction "35_35") (pintype "passive"))
    )
    (net (code "93") (name "/UART-CB_Rx") (class "Default")
      (node (ref "CN-A") (pin "22") (pinfunction "22_22") (pintype "passive"))
    )
    (net (code "94") (name "/UART-CB_Tx") (class "Default")
      (node (ref "CN-A") (pin "21") (pinfunction "21_21") (pintype "passive"))
    )
    (net (code "95") (name "/USB_5V") (class "Default")
      (node (ref "CN-A") (pin "10") (pinfunction "10_10") (pintype "passive"))
      (node (ref "CN-A") (pin "9") (pinfunction "9_9") (pintype "passive"))
    )
    (net (code "96") (name "/USB_DM1") (class "Default")
      (node (ref "CN-A") (pin "11") (pinfunction "11_11") (pintype "passive"))
      (node (ref "U1") (pin "25") (pinfunction "DM0_25") (pintype "passive"))
    )
    (net (code "97") (name "/USB_DM2") (class "Default")
      (node (ref "CN-A") (pin "12") (pinfunction "12_12") (pintype "passive"))
      (node (ref "U8") (pin "25") (pinfunction "DM0_25") (pintype "passive"))
    )
    (net (code "98") (name "/USB_DP1") (class "Default")
      (node (ref "CN-A") (pin "13") (pinfunction "13_13") (pintype "passive"))
      (node (ref "U1") (pin "26") (pinfunction "DP0_26") (pintype "passive"))
    )
    (net (code "99") (name "/USB_DP2") (class "Default")
      (node (ref "CN-A") (pin "14") (pinfunction "14_14") (pintype "passive"))
      (node (ref "U8") (pin "26") (pinfunction "DP0_26") (pintype "passive"))
    )
    (net (code "100") (name "/USB_POWER") (class "Default")
      (node (ref "CN-A") (pin "30") (pinfunction "30_30") (pintype "passive"))
      (node (ref "DCR1") (pin "3") (pinfunction "*INH_3") (pintype "bidirectional"))
    )
    (net (code "101") (name "/US_EMG") (class "Default")
      (node (ref "CN-A") (pin "26") (pinfunction "26_26") (pintype "passive"))
    )
    (net (code "102") (name "/US_POWER") (class "Default")
      (node (ref "CN-A") (pin "32") (pinfunction "32_32") (pintype "passive"))
    )
    (net (code "103") (name "DC5VB") (class "Default")
      (node (ref "C14") (pin "1") (pinfunction "1_1") (pintype "passive"))
      (node (ref "C16") (pin "1") (pinfunction "1_1") (pintype "passive"))
      (node (ref "C18") (pin "1") (pinfunction "1_1") (pintype "passive"))
      (node (ref "C20") (pin "1") (pinfunction "1_1") (pintype "passive"))
      (node (ref "C22") (pin "1") (pinfunction "1_1") (pintype "passive"))
      (node (ref "C24") (pin "1") (pinfunction "1_1") (pintype "passive"))
      (node (ref "C3") (pin "1") (pinfunction "1_1") (pintype "passive"))
      (node (ref "DCR1") (pin "5") (pinfunction "SENS_5") (pintype "bidirectional"))
      (node (ref "DCR1") (pin "6") (pinfunction "VO_6") (pintype "power_in"))
      (node (ref "F1") (pin "1") (pinfunction "1_1") (pintype "passive"))
      (node (ref "F2") (pin "1") (pinfunction "1_1") (pintype "passive"))
      (node (ref "F3") (pin "1") (pinfunction "1_1") (pintype "passive"))
      (node (ref "J1") (pin "1") (pinfunction "1_1") (pintype "passive"))
      (node (ref "J2") (pin "1") (pinfunction "1_1") (pintype "passive"))
      (node (ref "J3") (pin "1") (pinfunction "1_1") (pintype "passive"))
      (node (ref "J4") (pin "1") (pinfunction "1_1") (pintype "passive"))
      (node (ref "J5") (pin "1") (pinfunction "1_1") (pintype "passive"))
      (node (ref "J6") (pin "1") (pinfunction "1_1") (pintype "passive"))
      (node (ref "U1") (pin "23") (pinfunction "V5_23") (pintype "passive"))
      (node (ref "U2") (pin "7") (pinfunction "VDD_5_7") (pintype "passive"))
      (node (ref "U3") (pin "7") (pinfunction "VDD_5_7") (pintype "passive"))
      (node (ref "U4") (pin "7") (pinfunction "VDD_5_7") (pintype "passive"))
      (node (ref "U5") (pin "7") (pinfunction "VDD_5_7") (pintype "passive"))
      (node (ref "U6") (pin "7") (pinfunction "VDD_5_7") (pintype "passive"))
      (node (ref "U7") (pin "7") (pinfunction "VDD_5_7") (pintype "passive"))
      (node (ref "U8") (pin "23") (pinfunction "V5_23") (pintype "passive"))
    )
    (net (code "104") (name "DC24V") (class "Default")
      (node (ref "C1") (pin "2") (pinfunction "2_2") (pintype "passive"))
      (node (ref "C2") (pin "1") (pinfunction "1_1") (pintype "passive"))
      (node (ref "CN-A") (pin "1") (pinfunction "1_1") (pintype "passive"))
      (node (ref "CN-A") (pin "2") (pinfunction "2_2") (pintype "passive"))
      (node (ref "DCR1") (pin "2") (pinfunction "VI_2") (pintype "power_in"))
    )
    (net (code "105") (name "GND") (class "Default")
      (node (ref "C1") (pin "1") (pinfunction "1_1") (pintype "passive"))
      (node (ref "C10") (pin "1") (pinfunction "1_1") (pintype "passive"))
      (node (ref "C11") (pin "1") (pinfunction "1_1") (pintype "passive"))
      (node (ref "C12") (pin "1") (pinfunction "1_1") (pintype "passive"))
      (node (ref "C13") (pin "1") (pinfunction "1_1") (pintype "passive"))
      (node (ref "C14") (pin "2") (pinfunction "2_2") (pintype "passive"))
      (node (ref "C15") (pin "2") (pinfunction "2_2") (pintype "passive"))
      (node (ref "C16") (pin "2") (pinfunction "2_2") (pintype "passive"))
      (node (ref "C17") (pin "2") (pinfunction "2_2") (pintype "passive"))
      (node (ref "C18") (pin "2") (pinfunction "2_2") (pintype "passive"))
      (node (ref "C19") (pin "2") (pinfunction "2_2") (pintype "passive"))
      (node (ref "C2") (pin "2") (pinfunction "2_2") (pintype "passive"))
      (node (ref "C20") (pin "2") (pinfunction "2_2") (pintype "passive"))
      (node (ref "C21") (pin "2") (pinfunction "2_2") (pintype "passive"))
      (node (ref "C22") (pin "2") (pinfunction "2_2") (pintype "passive"))
      (node (ref "C23") (pin "2") (pinfunction "2_2") (pintype "passive"))
      (node (ref "C24") (pin "2") (pinfunction "2_2") (pintype "passive"))
      (node (ref "C25") (pin "2") (pinfunction "2_2") (pintype "passive"))
      (node (ref "C26") (pin "1") (pinfunction "1_1") (pintype "passive"))
      (node (ref "C27") (pin "1") (pinfunction "1_1") (pintype "passive"))
      (node (ref "C28") (pin "1") (pinfunction "1_1") (pintype "passive"))
      (node (ref "C29") (pin "2") (pinfunction "2_2") (pintype "passive"))
      (node (ref "C3") (pin "2") (pinfunction "2_2") (pintype "passive"))
      (node (ref "C30") (pin "1") (pinfunction "1_1") (pintype "passive"))
      (node (ref "C31") (pin "1") (pinfunction "1_1") (pintype "passive"))
      (node (ref "C32") (pin "1") (pinfunction "1_1") (pintype "passive"))
      (node (ref "C33") (pin "1") (pinfunction "1_1") (pintype "passive"))
      (node (ref "C34") (pin "1") (pinfunction "1_1") (pintype "passive"))
      (node (ref "C35") (pin "1") (pinfunction "1_1") (pintype "passive"))
      (node (ref "C4") (pin "1") (pinfunction "1_1") (pintype "passive"))
      (node (ref "C5") (pin "1") (pinfunction "1_1") (pintype "passive"))
      (node (ref "C6") (pin "1") (pinfunction "1_1") (pintype "passive"))
      (node (ref "C7") (pin "2") (pinfunction "2_2") (pintype "passive"))
      (node (ref "C8") (pin "1") (pinfunction "1_1") (pintype "passive"))
      (node (ref "C9") (pin "1") (pinfunction "1_1") (pintype "passive"))
      (node (ref "CN-A") (pin "35") (pinfunction "35_35") (pintype "passive"))
      (node (ref "CN-A") (pin "36") (pinfunction "36_36") (pintype "passive"))
      (node (ref "CN-A") (pin "37") (pinfunction "37_37") (pintype "passive"))
      (node (ref "CN-A") (pin "38") (pinfunction "38_38") (pintype "passive"))
      (node (ref "CN-A") (pin "39") (pinfunction "39_39") (pintype "passive"))
      (node (ref "CN-A") (pin "40") (pinfunction "40_40") (pintype "passive"))
      (node (ref "CN-B") (pin "39") (pinfunction "39_39") (pintype "passive"))
      (node (ref "CN-B") (pin "40") (pinfunction "40_40") (pintype "passive"))
      (node (ref "CN-C") (pin "39") (pinfunction "39_39") (pintype "passive"))
      (node (ref "CN-C") (pin "40") (pinfunction "40_40") (pintype "passive"))
      (node (ref "DCR1") (pin "1") (pinfunction "GND_1") (pintype "power_in"))
      (node (ref "DCR1") (pin "7") (pinfunction "GND_7") (pintype "power_in"))
      (node (ref "J1") (pin "4") (pinfunction "4_4") (pintype "passive"))
      (node (ref "J2") (pin "4") (pinfunction "4_4") (pintype "passive"))
      (node (ref "J3") (pin "4") (pinfunction "4_4") (pintype "passive"))
      (node (ref "J4") (pin "4") (pinfunction "4_4") (pintype "passive"))
      (node (ref "J5") (pin "4") (pinfunction "4_4") (pintype "passive"))
      (node (ref "J6") (pin "4") (pinfunction "4_4") (pintype "passive"))
      (node (ref "J7") (pin "4") (pinfunction "4_4") (pintype "passive"))
      (node (ref "J8") (pin "4") (pinfunction "4_4") (pintype "passive"))
      (node (ref "J9") (pin "4") (pinfunction "4_4") (pintype "passive"))
      (node (ref "R2") (pin "1") (pinfunction "1_1") (pintype "passive"))
      (node (ref "R27") (pin "1") (pinfunction "1_1") (pintype "passive"))
      (node (ref "R28") (pin "1") (pinfunction "1_1") (pintype "passive"))
      (node (ref "R3") (pin "1") (pinfunction "1_1") (pintype "passive"))
      (node (ref "R31") (pin "1") (pinfunction "1_1") (pintype "passive"))
      (node (ref "R40") (pin "1") (pinfunction "1_1") (pintype "passive"))
      (node (ref "R7") (pin "1") (pinfunction "1_1") (pintype "passive"))
      (node (ref "U2") (pin "1") (pinfunction "GND_1") (pintype "passive"))
      (node (ref "U3") (pin "1") (pinfunction "GND_1") (pintype "passive"))
      (node (ref "U4") (pin "1") (pinfunction "GND_1") (pintype "passive"))
      (node (ref "U5") (pin "1") (pinfunction "GND_1") (pintype "passive"))
      (node (ref "U6") (pin "1") (pinfunction "GND_1") (pintype "passive"))
      (node (ref "U7") (pin "1") (pinfunction "GND_1") (pintype "passive"))
      (node (ref "X1") (pin "2") (pinfunction "GND_2") (pintype "passive"))
      (node (ref "X1") (pin "4") (pinfunction "GND_4") (pintype "passive"))
      (node (ref "X2") (pin "2") (pinfunction "GND_2") (pintype "passive"))
      (node (ref "X2") (pin "4") (pinfunction "GND_4") (pintype "passive"))
    )
    (net (code "106") (name "HUB_33V1") (class "Default")
      (node (ref "C11") (pin "2") (pinfunction "2_2") (pintype "passive"))
      (node (ref "C12") (pin "2") (pinfunction "2_2") (pintype "passive"))
      (node (ref "C7") (pin "1") (pinfunction "1_1") (pintype "passive"))
      (node (ref "L1") (pin "2") (pinfunction "2_2") (pintype "passive"))
      (node (ref "R4") (pin "1") (pinfunction "1_1") (pintype "passive"))
      (node (ref "R5") (pin "1") (pinfunction "1_1") (pintype "passive"))
      (node (ref "R6") (pin "2") (pinfunction "2_2") (pintype "passive"))
      (node (ref "R8") (pin "2") (pinfunction "2_2") (pintype "passive"))
      (node (ref "U1") (pin "16") (pinfunction "DVDD_16") (pintype "passive"))
      (node (ref "U1") (pin "24") (pinfunction "V33_24") (pintype "passive"))
      (node (ref "U2") (pin "3") (pinfunction "VDD_325_3") (pintype "passive"))
      (node (ref "U3") (pin "3") (pinfunction "VDD_325_3") (pintype "passive"))
      (node (ref "U4") (pin "3") (pinfunction "VDD_325_3") (pintype "passive"))
    )
    (net (code "107") (name "HUB_33V2") (class "Default")
      (node (ref "C29") (pin "1") (pinfunction "1_1") (pintype "passive"))
      (node (ref "C33") (pin "2") (pinfunction "2_2") (pintype "passive"))
      (node (ref "C34") (pin "2") (pinfunction "2_2") (pintype "passive"))
      (node (ref "L2") (pin "2") (pinfunction "2_2") (pintype "passive"))
      (node (ref "R29") (pin "1") (pinfunction "1_1") (pintype "passive"))
      (node (ref "R30") (pin "1") (pinfunction "1_1") (pintype "passive"))
      (node (ref "R32") (pin "2") (pinfunction "2_2") (pintype "passive"))
      (node (ref "R33") (pin "2") (pinfunction "2_2") (pintype "passive"))
      (node (ref "U5") (pin "3") (pinfunction "VDD_325_3") (pintype "passive"))
      (node (ref "U6") (pin "3") (pinfunction "VDD_325_3") (pintype "passive"))
      (node (ref "U7") (pin "3") (pinfunction "VDD_325_3") (pintype "passive"))
      (node (ref "U8") (pin "16") (pinfunction "DVDD_16") (pintype "passive"))
      (node (ref "U8") (pin "24") (pinfunction "V33_24") (pintype "passive"))
    )
    (net (code "108") (name "Net-(DCR1-ADJ)") (class "Default")
      (node (ref "DCR1") (pin "4") (pinfunction "ADJ_4") (pintype "bidirectional"))
      (node (ref "R1") (pin "2") (pinfunction "2_2") (pintype "passive"))
    )
    (net (code "109") (name "Net-(F1-Pad2)") (class "Default")
      (node (ref "F1") (pin "2") (pinfunction "2_2") (pintype "passive"))
      (node (ref "J7") (pin "1") (pinfunction "1_1") (pintype "passive"))
    )
    (net (code "110") (name "Net-(F2-Pad2)") (class "Default")
      (node (ref "F2") (pin "2") (pinfunction "2_2") (pintype "passive"))
      (node (ref "J8") (pin "1") (pinfunction "1_1") (pintype "passive"))
    )
    (net (code "111") (name "Net-(F3-Pad2)") (class "Default")
      (node (ref "F3") (pin "2") (pinfunction "2_2") (pintype "passive"))
      (node (ref "J9") (pin "1") (pinfunction "1_1") (pintype "passive"))
    )
    (net (code "112") (name "Net-(R1-Pad1)") (class "Default")
      (node (ref "R1") (pin "1") (pinfunction "1_1") (pintype "passive"))
      (node (ref "R40") (pin "2") (pinfunction "2_2") (pintype "passive"))
    )
    (net (code "113") (name "Net-(U1-AVDD1)") (class "Default")
      (node (ref "C10") (pin "2") (pinfunction "2_2") (pintype "passive"))
      (node (ref "C6") (pin "2") (pinfunction "2_2") (pintype "passive"))
      (node (ref "C8") (pin "2") (pinfunction "2_2") (pintype "passive"))
      (node (ref "C9") (pin "2") (pinfunction "2_2") (pintype "passive"))
      (node (ref "L1") (pin "1") (pinfunction "1_1") (pintype "passive"))
      (node (ref "U1") (pin "1") (pinfunction "AVDD1_1") (pintype "passive"))
      (node (ref "U1") (pin "10") (pinfunction "AVDD3_10") (pintype "passive"))
      (node (ref "U1") (pin "5") (pinfunction "AVDD2_5") (pintype "passive"))
    )
    (net (code "114") (name "Net-(U1-OVCUR1#)") (class "Default")
      (node (ref "R6") (pin "1") (pinfunction "1_1") (pintype "passive"))
      (node (ref "R7") (pin "2") (pinfunction "2_2") (pintype "passive"))
      (node (ref "U1") (pin "21") (pinfunction "OVCUR1#_21") (pintype "passive"))
    )
    (net (code "115") (name "Net-(U1-PGANG)") (class "Default")
      (node (ref "R4") (pin "2") (pinfunction "2_2") (pintype "passive"))
      (node (ref "U1") (pin "18") (pinfunction "PGANG_18") (pintype "passive"))
    )
    (net (code "116") (name "Net-(U1-PSELF)") (class "Default")
      (node (ref "R5") (pin "2") (pinfunction "2_2") (pintype "passive"))
      (node (ref "U1") (pin "17") (pinfunction "PSELF_17") (pintype "passive"))
    )
    (net (code "117") (name "Net-(U1-RESET)") (class "Default")
      (node (ref "C13") (pin "2") (pinfunction "2_2") (pintype "passive"))
      (node (ref "R8") (pin "1") (pinfunction "1_1") (pintype "passive"))
      (node (ref "U1") (pin "13") (pinfunction "RESET_13") (pintype "passive"))
    )
    (net (code "118") (name "Net-(U1-RREF)") (class "Default")
      (node (ref "R2") (pin "2") (pinfunction "2_2") (pintype "passive"))
      (node (ref "U1") (pin "4") (pinfunction "RREF_4") (pintype "passive"))
    )
    (net (code "119") (name "Net-(U1-TEST)") (class "Default")
      (node (ref "R3") (pin "2") (pinfunction "2_2") (pintype "passive"))
      (node (ref "U1") (pin "14") (pinfunction "TEST_14") (pintype "passive"))
    )
    (net (code "120") (name "Net-(U1-XTAL1)") (class "Default")
      (node (ref "C4") (pin "2") (pinfunction "2_2") (pintype "passive"))
      (node (ref "U1") (pin "6") (pinfunction "XTAL1_6") (pintype "passive"))
      (node (ref "X1") (pin "1") (pinfunction "X1_1") (pintype "passive"))
    )
    (net (code "121") (name "Net-(U1-XTAL2)") (class "Default")
      (node (ref "C5") (pin "2") (pinfunction "2_2") (pintype "passive"))
      (node (ref "U1") (pin "7") (pinfunction "XTAL2_7") (pintype "passive"))
      (node (ref "X1") (pin "3") (pinfunction "X2_3") (pintype "passive"))
    )
    (net (code "122") (name "Net-(U2-DM)") (class "Default")
      (node (ref "R10") (pin "2") (pinfunction "2_2") (pintype "passive"))
      (node (ref "U2") (pin "6") (pinfunction "DM_6") (pintype "passive"))
    )
    (net (code "123") (name "Net-(U2-DP)") (class "Default")
      (node (ref "R11") (pin "2") (pinfunction "2_2") (pintype "passive"))
      (node (ref "U2") (pin "5") (pinfunction "DP_5") (pintype "passive"))
    )
    (net (code "124") (name "Net-(U2-RXD)") (class "Default")
      (node (ref "J1") (pin "3") (pinfunction "3_3") (pintype "passive"))
      (node (ref "U2") (pin "4") (pinfunction "RXD_4") (pintype "passive"))
    )
    (net (code "125") (name "Net-(U2-TXD)") (class "Default")
      (node (ref "J1") (pin "2") (pinfunction "2_2") (pintype "passive"))
      (node (ref "U2") (pin "2") (pinfunction "TXD_2") (pintype "passive"))
    )
    (net (code "126") (name "Net-(U2-VDD_33)") (class "Default")
      (node (ref "C15") (pin "1") (pinfunction "1_1") (pintype "passive"))
      (node (ref "R9") (pin "2") (pinfunction "2_2") (pintype "passive"))
      (node (ref "U2") (pin "8") (pinfunction "VDD_33_8") (pintype "passive"))
    )
    (net (code "127") (name "Net-(U3-DM)") (class "Default")
      (node (ref "R13") (pin "2") (pinfunction "2_2") (pintype "passive"))
      (node (ref "U3") (pin "6") (pinfunction "DM_6") (pintype "passive"))
    )
    (net (code "128") (name "Net-(U3-DP)") (class "Default")
      (node (ref "R14") (pin "2") (pinfunction "2_2") (pintype "passive"))
      (node (ref "U3") (pin "5") (pinfunction "DP_5") (pintype "passive"))
    )
    (net (code "129") (name "Net-(U3-RXD)") (class "Default")
      (node (ref "J2") (pin "3") (pinfunction "3_3") (pintype "passive"))
      (node (ref "U3") (pin "4") (pinfunction "RXD_4") (pintype "passive"))
    )
    (net (code "130") (name "Net-(U3-TXD)") (class "Default")
      (node (ref "J2") (pin "2") (pinfunction "2_2") (pintype "passive"))
      (node (ref "U3") (pin "2") (pinfunction "TXD_2") (pintype "passive"))
    )
    (net (code "131") (name "Net-(U3-VDD_33)") (class "Default")
      (node (ref "C17") (pin "1") (pinfunction "1_1") (pintype "passive"))
      (node (ref "R12") (pin "2") (pinfunction "2_2") (pintype "passive"))
      (node (ref "U3") (pin "8") (pinfunction "VDD_33_8") (pintype "passive"))
    )
    (net (code "132") (name "Net-(U4-DM)") (class "Default")
      (node (ref "R16") (pin "2") (pinfunction "2_2") (pintype "passive"))
      (node (ref "U4") (pin "6") (pinfunction "DM_6") (pintype "passive"))
    )
    (net (code "133") (name "Net-(U4-DP)") (class "Default")
      (node (ref "R17") (pin "2") (pinfunction "2_2") (pintype "passive"))
      (node (ref "U4") (pin "5") (pinfunction "DP_5") (pintype "passive"))
    )
    (net (code "134") (name "Net-(U4-RXD)") (class "Default")
      (node (ref "J3") (pin "3") (pinfunction "3_3") (pintype "passive"))
      (node (ref "U4") (pin "4") (pinfunction "RXD_4") (pintype "passive"))
    )
    (net (code "135") (name "Net-(U4-TXD)") (class "Default")
      (node (ref "J3") (pin "2") (pinfunction "2_2") (pintype "passive"))
      (node (ref "U4") (pin "2") (pinfunction "TXD_2") (pintype "passive"))
    )
    (net (code "136") (name "Net-(U4-VDD_33)") (class "Default")
      (node (ref "C19") (pin "1") (pinfunction "1_1") (pintype "passive"))
      (node (ref "R15") (pin "2") (pinfunction "2_2") (pintype "passive"))
      (node (ref "U4") (pin "8") (pinfunction "VDD_33_8") (pintype "passive"))
    )
    (net (code "137") (name "Net-(U5-DM)") (class "Default")
      (node (ref "R19") (pin "2") (pinfunction "2_2") (pintype "passive"))
      (node (ref "U5") (pin "6") (pinfunction "DM_6") (pintype "passive"))
    )
    (net (code "138") (name "Net-(U5-DP)") (class "Default")
      (node (ref "R20") (pin "2") (pinfunction "2_2") (pintype "passive"))
      (node (ref "U5") (pin "5") (pinfunction "DP_5") (pintype "passive"))
    )
    (net (code "139") (name "Net-(U5-RXD)") (class "Default")
      (node (ref "J4") (pin "3") (pinfunction "3_3") (pintype "passive"))
      (node (ref "U5") (pin "4") (pinfunction "RXD_4") (pintype "passive"))
    )
    (net (code "140") (name "Net-(U5-TXD)") (class "Default")
      (node (ref "J4") (pin "2") (pinfunction "2_2") (pintype "passive"))
      (node (ref "U5") (pin "2") (pinfunction "TXD_2") (pintype "passive"))
    )
    (net (code "141") (name "Net-(U5-VDD_33)") (class "Default")
      (node (ref "C21") (pin "1") (pinfunction "1_1") (pintype "passive"))
      (node (ref "R18") (pin "2") (pinfunction "2_2") (pintype "passive"))
      (node (ref "U5") (pin "8") (pinfunction "VDD_33_8") (pintype "passive"))
    )
    (net (code "142") (name "Net-(U6-DM)") (class "Default")
      (node (ref "R22") (pin "2") (pinfunction "2_2") (pintype "passive"))
      (node (ref "U6") (pin "6") (pinfunction "DM_6") (pintype "passive"))
    )
    (net (code "143") (name "Net-(U6-DP)") (class "Default")
      (node (ref "R23") (pin "2") (pinfunction "2_2") (pintype "passive"))
      (node (ref "U6") (pin "5") (pinfunction "DP_5") (pintype "passive"))
    )
    (net (code "144") (name "Net-(U6-RXD)") (class "Default")
      (node (ref "J5") (pin "3") (pinfunction "3_3") (pintype "passive"))
      (node (ref "U6") (pin "4") (pinfunction "RXD_4") (pintype "passive"))
    )
    (net (code "145") (name "Net-(U6-TXD)") (class "Default")
      (node (ref "J5") (pin "2") (pinfunction "2_2") (pintype "passive"))
      (node (ref "U6") (pin "2") (pinfunction "TXD_2") (pintype "passive"))
    )
    (net (code "146") (name "Net-(U6-VDD_33)") (class "Default")
      (node (ref "C23") (pin "1") (pinfunction "1_1") (pintype "passive"))
      (node (ref "R21") (pin "2") (pinfunction "2_2") (pintype "passive"))
      (node (ref "U6") (pin "8") (pinfunction "VDD_33_8") (pintype "passive"))
    )
    (net (code "147") (name "Net-(U7-DM)") (class "Default")
      (node (ref "R25") (pin "2") (pinfunction "2_2") (pintype "passive"))
      (node (ref "U7") (pin "6") (pinfunction "DM_6") (pintype "passive"))
    )
    (net (code "148") (name "Net-(U7-DP)") (class "Default")
      (node (ref "R26") (pin "2") (pinfunction "2_2") (pintype "passive"))
      (node (ref "U7") (pin "5") (pinfunction "DP_5") (pintype "passive"))
    )
    (net (code "149") (name "Net-(U7-RXD)") (class "Default")
      (node (ref "J6") (pin "3") (pinfunction "3_3") (pintype "passive"))
      (node (ref "U7") (pin "4") (pinfunction "RXD_4") (pintype "passive"))
    )
    (net (code "150") (name "Net-(U7-TXD)") (class "Default")
      (node (ref "J6") (pin "2") (pinfunction "2_2") (pintype "passive"))
      (node (ref "U7") (pin "2") (pinfunction "TXD_2") (pintype "passive"))
    )
    (net (code "151") (name "Net-(U7-VDD_33)") (class "Default")
      (node (ref "C25") (pin "1") (pinfunction "1_1") (pintype "passive"))
      (node (ref "R24") (pin "2") (pinfunction "2_2") (pintype "passive"))
      (node (ref "U7") (pin "8") (pinfunction "VDD_33_8") (pintype "passive"))
    )
    (net (code "152") (name "Net-(U8-AVDD1)") (class "Default")
      (node (ref "C28") (pin "2") (pinfunction "2_2") (pintype "passive"))
      (node (ref "C30") (pin "2") (pinfunction "2_2") (pintype "passive"))
      (node (ref "C31") (pin "2") (pinfunction "2_2") (pintype "passive"))
      (node (ref "C32") (pin "2") (pinfunction "2_2") (pintype "passive"))
      (node (ref "L2") (pin "1") (pinfunction "1_1") (pintype "passive"))
      (node (ref "U8") (pin "1") (pinfunction "AVDD1_1") (pintype "passive"))
      (node (ref "U8") (pin "10") (pinfunction "AVDD3_10") (pintype "passive"))
      (node (ref "U8") (pin "5") (pinfunction "AVDD2_5") (pintype "passive"))
    )
    (net (code "153") (name "Net-(U8-OVCUR1#)") (class "Default")
      (node (ref "R31") (pin "2") (pinfunction "2_2") (pintype "passive"))
      (node (ref "R32") (pin "1") (pinfunction "1_1") (pintype "passive"))
      (node (ref "U8") (pin "21") (pinfunction "OVCUR1#_21") (pintype "passive"))
    )
    (net (code "154") (name "Net-(U8-PGANG)") (class "Default")
      (node (ref "R29") (pin "2") (pinfunction "2_2") (pintype "passive"))
      (node (ref "U8") (pin "18") (pinfunction "PGANG_18") (pintype "passive"))
    )
    (net (code "155") (name "Net-(U8-PSELF)") (class "Default")
      (node (ref "R30") (pin "2") (pinfunction "2_2") (pintype "passive"))
      (node (ref "U8") (pin "17") (pinfunction "PSELF_17") (pintype "passive"))
    )
    (net (code "156") (name "Net-(U8-RESET)") (class "Default")
      (node (ref "C35") (pin "2") (pinfunction "2_2") (pintype "passive"))
      (node (ref "R33") (pin "1") (pinfunction "1_1") (pintype "passive"))
      (node (ref "U8") (pin "13") (pinfunction "RESET_13") (pintype "passive"))
    )
    (net (code "157") (name "Net-(U8-RREF)") (class "Default")
      (node (ref "R27") (pin "2") (pinfunction "2_2") (pintype "passive"))
      (node (ref "U8") (pin "4") (pinfunction "RREF_4") (pintype "passive"))
    )
    (net (code "158") (name "Net-(U8-TEST)") (class "Default")
      (node (ref "R28") (pin "2") (pinfunction "2_2") (pintype "passive"))
      (node (ref "U8") (pin "14") (pinfunction "TEST_14") (pintype "passive"))
    )
    (net (code "159") (name "Net-(U8-XTAL1)") (class "Default")
      (node (ref "C26") (pin "2") (pinfunction "2_2") (pintype "passive"))
      (node (ref "U8") (pin "6") (pinfunction "XTAL1_6") (pintype "passive"))
      (node (ref "X2") (pin "1") (pinfunction "X1_1") (pintype "passive"))
    )
    (net (code "160") (name "Net-(U8-XTAL2)") (class "Default")
      (node (ref "C27") (pin "2") (pinfunction "2_2") (pintype "passive"))
      (node (ref "U8") (pin "7") (pinfunction "XTAL2_7") (pintype "passive"))
      (node (ref "X2") (pin "3") (pinfunction "X2_3") (pintype "passive"))
    )
    (net (code "161") (name "unconnected-(CN-A-Pad15)") (class "Default")
      (node (ref "CN-A") (pin "15") (pinfunction "15_15") (pintype "passive"))
    )
    (net (code "162") (name "unconnected-(CN-A-Pad16)") (class "Default")
      (node (ref "CN-A") (pin "16") (pinfunction "16_16") (pintype "passive"))
    )
    (net (code "163") (name "unconnected-(CN-A-Pad23)") (class "Default")
      (node (ref "CN-A") (pin "23") (pinfunction "23_23") (pintype "passive"))
    )
    (net (code "164") (name "unconnected-(CN-A-Pad24)") (class "Default")
      (node (ref "CN-A") (pin "24") (pinfunction "24_24") (pintype "passive"))
    )
    (net (code "165") (name "unconnected-(CN-A-Pad27)") (class "Default")
      (node (ref "CN-A") (pin "27") (pinfunction "27_27") (pintype "passive"))
    )
    (net (code "166") (name "unconnected-(CN-A-Pad28)") (class "Default")
      (node (ref "CN-A") (pin "28") (pinfunction "28_28") (pintype "passive"))
    )
    (net (code "167") (name "unconnected-(CN-A-Pad34)") (class "Default")
      (node (ref "CN-A") (pin "34") (pinfunction "34_34") (pintype "passive"))
    )
    (net (code "168") (name "unconnected-(CN-B-Pad2)") (class "Default")
      (node (ref "CN-B") (pin "2") (pinfunction "2_2") (pintype "passive"))
    )
    (net (code "169") (name "unconnected-(CN-B-Pad4)") (class "Default")
      (node (ref "CN-B") (pin "4") (pinfunction "4_4") (pintype "passive"))
    )
    (net (code "170") (name "unconnected-(CN-B-Pad6)") (class "Default")
      (node (ref "CN-B") (pin "6") (pinfunction "6_6") (pintype "passive"))
    )
    (net (code "171") (name "unconnected-(CN-B-Pad20)") (class "Default")
      (node (ref "CN-B") (pin "20") (pinfunction "20_20") (pintype "passive"))
    )
    (net (code "172") (name "unconnected-(CN-B-Pad22)") (class "Default")
      (node (ref "CN-B") (pin "22") (pinfunction "22_22") (pintype "passive"))
    )
    (net (code "173") (name "unconnected-(CN-B-Pad24)") (class "Default")
      (node (ref "CN-B") (pin "24") (pinfunction "24_24") (pintype "passive"))
    )
    (net (code "174") (name "unconnected-(CN-B-Pad26)") (class "Default")
      (node (ref "CN-B") (pin "26") (pinfunction "26_26") (pintype "passive"))
    )
    (net (code "175") (name "unconnected-(CN-B-Pad27)") (class "Default")
      (node (ref "CN-B") (pin "27") (pinfunction "27_27") (pintype "passive"))
    )
    (net (code "176") (name "unconnected-(CN-B-Pad28)") (class "Default")
      (node (ref "CN-B") (pin "28") (pinfunction "28_28") (pintype "passive"))
    )
    (net (code "177") (name "unconnected-(CN-B-Pad29)") (class "Default")
      (node (ref "CN-B") (pin "29") (pinfunction "29_29") (pintype "passive"))
    )
    (net (code "178") (name "unconnected-(CN-B-Pad30)") (class "Default")
      (node (ref "CN-B") (pin "30") (pinfunction "30_30") (pintype "passive"))
    )
    (net (code "179") (name "unconnected-(CN-B-Pad31)") (class "Default")
      (node (ref "CN-B") (pin "31") (pinfunction "31_31") (pintype "passive"))
    )
    (net (code "180") (name "unconnected-(CN-B-Pad32)") (class "Default")
      (node (ref "CN-B") (pin "32") (pinfunction "32_32") (pintype "passive"))
    )
    (net (code "181") (name "unconnected-(CN-B-Pad37)") (class "Default")
      (node (ref "CN-B") (pin "37") (pinfunction "37_37") (pintype "passive"))
    )
    (net (code "182") (name "unconnected-(CN-B-Pad38)") (class "Default")
      (node (ref "CN-B") (pin "38") (pinfunction "38_38") (pintype "passive"))
    )
    (net (code "183") (name "unconnected-(U1-GND-Pad15)") (class "Default")
      (node (ref "U1") (pin "15") (pinfunction "GND_15") (pintype "passive"))
    )
    (net (code "184") (name "unconnected-(U1-OVCUR2#-Pad19)") (class "Default")
      (node (ref "U1") (pin "19") (pinfunction "OVCUR2#_19") (pintype "passive"))
    )
    (net (code "185") (name "unconnected-(U1-PWREN1-Pad22)") (class "Default")
      (node (ref "U1") (pin "22") (pinfunction "PWREN1_22") (pintype "passive"))
    )
    (net (code "186") (name "unconnected-(U1-PWREN2-Pad20)") (class "Default")
      (node (ref "U1") (pin "20") (pinfunction "PWREN2_20") (pintype "passive"))
    )
    (net (code "187") (name "unconnected-(U8-GND-Pad15)") (class "Default")
      (node (ref "U8") (pin "15") (pinfunction "GND_15") (pintype "passive"))
    )
    (net (code "188") (name "unconnected-(U8-OVCUR2#-Pad19)") (class "Default")
      (node (ref "U8") (pin "19") (pinfunction "OVCUR2#_19") (pintype "passive"))
    )
    (net (code "189") (name "unconnected-(U8-PWREN1-Pad22)") (class "Default")
      (node (ref "U8") (pin "22") (pinfunction "PWREN1_22") (pintype "passive"))
    )
    (net (code "190") (name "unconnected-(U8-PWREN2-Pad20)") (class "Default")
      (node (ref "U8") (pin "20") (pinfunction "PWREN2_20") (pintype "passive"))
    )
  )
)
